# PowerBus.net
KiCad netlist of a schematic drawn in EAGLE
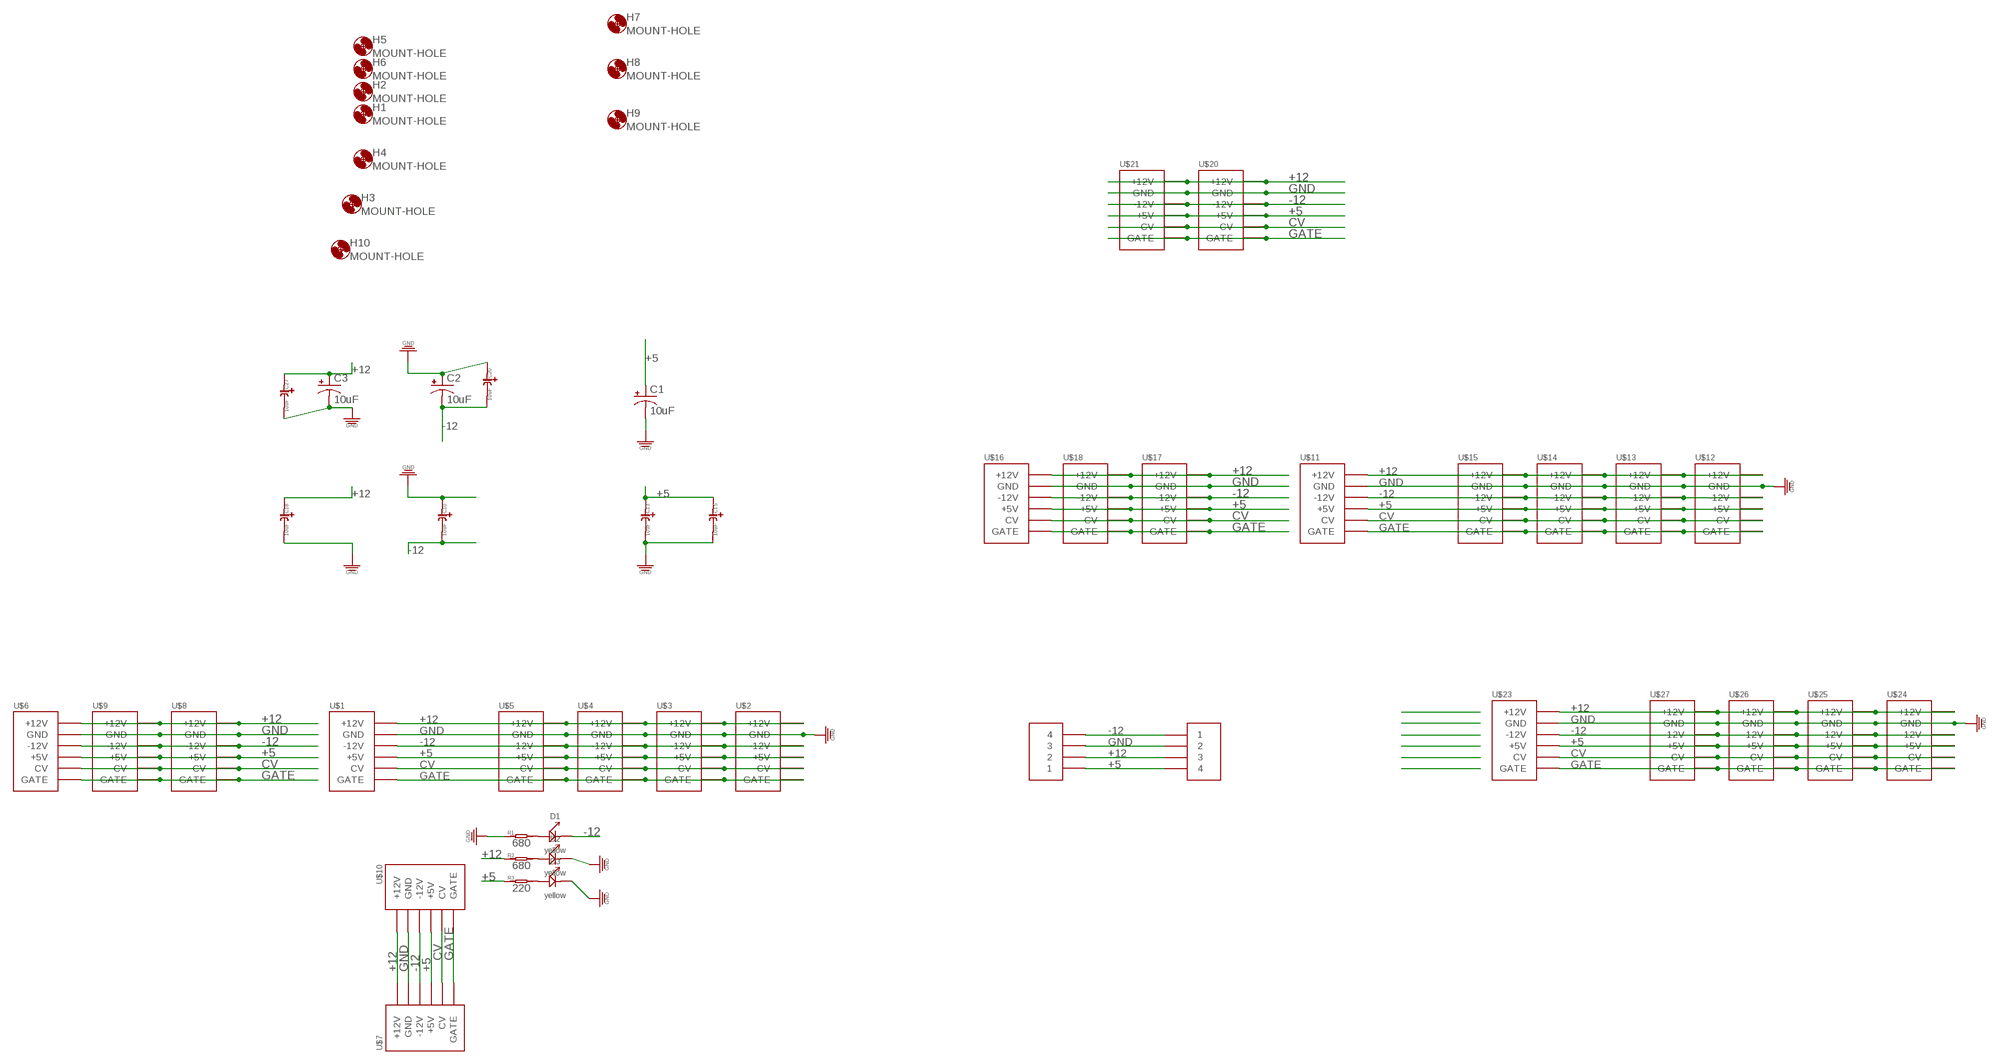
[diagram p0: schematic, sheet 1]

(export (version "E")
  (design (tool "Eeschema 10.0.6"))
  (components
    (comp (ref "C1")
      (value "10uF")
      (footprint "eagle-import:PANASONIC_D")
      (libsource (lib "eagle-import") (part "CAP_POLD"))
    )
    (comp (ref "C2")
      (value "10uF")
      (footprint "eagle-import:PANASONIC_D")
      (libsource (lib "eagle-import") (part "CAP_POLD"))
    )
    (comp (ref "C3")
      (value "10uF")
      (footprint "eagle-import:PANASONIC_D")
      (libsource (lib "eagle-import") (part "CAP_POLD"))
    )
    (comp (ref "C10")
      (value "10uF")
      (footprint "eagle-import:CASE-A_3216")
      (libsource (lib "eagle-import") (part "C-POLAR-A"))
    )
    (comp (ref "C13")
      (value "10uF")
      (footprint "eagle-import:CASE-A_3216")
      (libsource (lib "eagle-import") (part "C-POLAR-A"))
    )
    (comp (ref "C15")
      (value "10uF")
      (footprint "eagle-import:CASE-A_3216")
      (libsource (lib "eagle-import") (part "C-POLAR-A"))
    )
    (comp (ref "C18")
      (value "10uF")
      (footprint "eagle-import:CASE-A_3216")
      (libsource (lib "eagle-import") (part "C-POLAR-A"))
    )
    (comp (ref "C20")
      (value "10uF")
      (footprint "eagle-import:CASE-A_3216")
      (libsource (lib "eagle-import") (part "C-POLAR-A"))
    )
    (comp (ref "C27")
      (value "10uF")
      (footprint "eagle-import:CASE-A_3216")
      (libsource (lib "eagle-import") (part "C-POLAR-A"))
    )
    (comp (ref "D1")
      (value "yellow")
      (footprint "eagle-import:LED0603")
      (libsource (lib "eagle-import") (part "LED"))
    )
    (comp (ref "D2")
      (value "yellow")
      (footprint "eagle-import:LED0603")
      (libsource (lib "eagle-import") (part "LED"))
    )
    (comp (ref "D3")
      (value "yellow")
      (footprint "eagle-import:LED0603")
      (libsource (lib "eagle-import") (part "LED"))
    )
    (comp (ref "H1")
      (value "MOUNT-HOLE")
      (footprint "eagle-import:3.2-NOMARKINGS-SMALLSAFEZONE")
      (libsource (lib "eagle-import") (part "MOUNT-HOLE"))
    )
    (comp (ref "H2")
      (value "MOUNT-HOLE")
      (footprint "eagle-import:3.2-NOMARKINGS-SMALLSAFEZONE")
      (libsource (lib "eagle-import") (part "MOUNT-HOLE"))
    )
    (comp (ref "H3")
      (value "MOUNT-HOLE")
      (footprint "eagle-import:3.2-NOMARKINGS-SMALLSAFEZONE")
      (libsource (lib "eagle-import") (part "MOUNT-HOLE"))
    )
    (comp (ref "H4")
      (value "MOUNT-HOLE")
      (footprint "eagle-import:3.2-NOMARKINGS-SMALLSAFEZONE")
      (libsource (lib "eagle-import") (part "MOUNT-HOLE"))
    )
    (comp (ref "H5")
      (value "MOUNT-HOLE")
      (footprint "eagle-import:3.2-NOMARKINGS-SMALLSAFEZONE")
      (libsource (lib "eagle-import") (part "MOUNT-HOLE"))
    )
    (comp (ref "H6")
      (value "MOUNT-HOLE")
      (footprint "eagle-import:3.2-NOMARKINGS-SMALLSAFEZONE")
      (libsource (lib "eagle-import") (part "MOUNT-HOLE"))
    )
    (comp (ref "H7")
      (value "MOUNT-HOLE")
      (footprint "eagle-import:3.2-NOMARKINGS-SMALLSAFEZONE")
      (libsource (lib "eagle-import") (part "MOUNT-HOLE"))
    )
    (comp (ref "H8")
      (value "MOUNT-HOLE")
      (footprint "eagle-import:3.2-NOMARKINGS-SMALLSAFEZONE")
      (libsource (lib "eagle-import") (part "MOUNT-HOLE"))
    )
    (comp (ref "H9")
      (value "MOUNT-HOLE")
      (footprint "eagle-import:3.2-NOMARKINGS-SMALLSAFEZONE")
      (libsource (lib "eagle-import") (part "MOUNT-HOLE"))
    )
    (comp (ref "H10")
      (value "MOUNT-HOLE")
      (footprint "eagle-import:3.2-NOMARKINGS-SMALLSAFEZONE")
      (libsource (lib "eagle-import") (part "MOUNT-HOLE"))
    )
    (comp (ref "R1")
      (value "680")
      (footprint "eagle-import:R0603")
      (libsource (lib "eagle-import") (part "R-0603"))
    )
    (comp (ref "R2")
      (value "680")
      (footprint "eagle-import:R0603")
      (libsource (lib "eagle-import") (part "R-0603"))
    )
    (comp (ref "R3")
      (value "220")
      (footprint "eagle-import:R0603")
      (libsource (lib "eagle-import") (part "R-0603"))
    )
    (comp (ref "U$1")
      (value "POWER_SHROUDED_NOTEXT")
      (footprint "eagle-import:POWER_16_SHROUDED_NOTEXT")
      (libsource (lib "eagle-import") (part "POWER_SHROUDED_NOTEXT"))
    )
    (comp (ref "U$2")
      (value "POWER_SHROUDED_NOTEXT")
      (footprint "eagle-import:POWER_16_SHROUDED_NOTEXT")
      (libsource (lib "eagle-import") (part "POWER_SHROUDED_NOTEXT"))
    )
    (comp (ref "U$3")
      (value "POWER_SHROUDED_NOTEXT")
      (footprint "eagle-import:POWER_16_SHROUDED_NOTEXT")
      (libsource (lib "eagle-import") (part "POWER_SHROUDED_NOTEXT"))
    )
    (comp (ref "U$4")
      (value "POWER_SHROUDED_NOTEXT")
      (footprint "eagle-import:POWER_16_SHROUDED_NOTEXT")
      (libsource (lib "eagle-import") (part "POWER_SHROUDED_NOTEXT"))
    )
    (comp (ref "U$5")
      (value "POWER_SHROUDED_NOTEXT")
      (footprint "eagle-import:POWER_16_SHROUDED_NOTEXT")
      (libsource (lib "eagle-import") (part "POWER_SHROUDED_NOTEXT"))
    )
    (comp (ref "U$6")
      (value "POWER_SHROUDED_NOTEXT")
      (footprint "eagle-import:POWER_16_SHROUDED_NOTEXT")
      (libsource (lib "eagle-import") (part "POWER_SHROUDED_NOTEXT"))
    )
    (comp (ref "U$7")
      (value "POWER_SHROUDED_NOTEXT")
      (footprint "eagle-import:POWER_16_SHROUDED_NOTEXT")
      (libsource (lib "eagle-import") (part "POWER_SHROUDED_NOTEXT"))
    )
    (comp (ref "U$8")
      (value "POWER_SHROUDED_NOTEXT")
      (footprint "eagle-import:POWER_16_SHROUDED_NOTEXT")
      (libsource (lib "eagle-import") (part "POWER_SHROUDED_NOTEXT"))
    )
    (comp (ref "U$9")
      (value "POWER_SHROUDED_NOTEXT")
      (footprint "eagle-import:POWER_16_SHROUDED_NOTEXT")
      (libsource (lib "eagle-import") (part "POWER_SHROUDED_NOTEXT"))
    )
    (comp (ref "U$10")
      (value "POWER_SHROUDED_NOTEXT")
      (footprint "eagle-import:POWER_16_SHROUDED_NOTEXT")
      (libsource (lib "eagle-import") (part "POWER_SHROUDED_NOTEXT"))
    )
    (comp (ref "U$11")
      (value "POWER_SHROUDED_NOTEXT")
      (footprint "eagle-import:POWER_16_SHROUDED_NOTEXT")
      (libsource (lib "eagle-import") (part "POWER_SHROUDED_NOTEXT"))
    )
    (comp (ref "U$12")
      (value "POWER_SHROUDED_NOTEXT")
      (footprint "eagle-import:POWER_16_SHROUDED_NOTEXT")
      (libsource (lib "eagle-import") (part "POWER_SHROUDED_NOTEXT"))
    )
    (comp (ref "U$13")
      (value "POWER_SHROUDED_NOTEXT")
      (footprint "eagle-import:POWER_16_SHROUDED_NOTEXT")
      (libsource (lib "eagle-import") (part "POWER_SHROUDED_NOTEXT"))
    )
    (comp (ref "U$14")
      (value "POWER_SHROUDED_NOTEXT")
      (footprint "eagle-import:POWER_16_SHROUDED_NOTEXT")
      (libsource (lib "eagle-import") (part "POWER_SHROUDED_NOTEXT"))
    )
    (comp (ref "U$15")
      (value "POWER_SHROUDED_NOTEXT")
      (footprint "eagle-import:POWER_16_SHROUDED_NOTEXT")
      (libsource (lib "eagle-import") (part "POWER_SHROUDED_NOTEXT"))
    )
    (comp (ref "U$16")
      (value "POWER_SHROUDED_NOTEXT")
      (footprint "eagle-import:POWER_16_SHROUDED_NOTEXT")
      (libsource (lib "eagle-import") (part "POWER_SHROUDED_NOTEXT"))
    )
    (comp (ref "U$17")
      (value "POWER_SHROUDED_NOTEXT")
      (footprint "eagle-import:POWER_16_SHROUDED_NOTEXT")
      (libsource (lib "eagle-import") (part "POWER_SHROUDED_NOTEXT"))
    )
    (comp (ref "U$18")
      (value "POWER_SHROUDED_NOTEXT")
      (footprint "eagle-import:POWER_16_SHROUDED_NOTEXT")
      (libsource (lib "eagle-import") (part "POWER_SHROUDED_NOTEXT"))
    )
    (comp (ref "U$19")
      (value "4PIN5MM")
      (footprint "eagle-import:4PIN5MM")
      (libsource (lib "eagle-import") (part "4PIN5MM"))
    )
    (comp (ref "U$20")
      (value "POWER_SHROUDED_NOTEXT")
      (footprint "eagle-import:POWER_16_SHROUDED_NOTEXT")
      (libsource (lib "eagle-import") (part "POWER_SHROUDED_NOTEXT"))
    )
    (comp (ref "U$21")
      (value "POWER_SHROUDED_NOTEXT")
      (footprint "eagle-import:POWER_16_SHROUDED_NOTEXT")
      (libsource (lib "eagle-import") (part "POWER_SHROUDED_NOTEXT"))
    )
    (comp (ref "U$22")
      (value "4PIN5MM")
      (footprint "eagle-import:4PIN5MM")
      (libsource (lib "eagle-import") (part "4PIN5MM"))
    )
    (comp (ref "U$23")
      (value "POWER_SHROUDED_NOTEXT")
      (footprint "eagle-import:POWER_16_SHROUDED_NOTEXT")
      (libsource (lib "eagle-import") (part "POWER_SHROUDED_NOTEXT"))
    )
    (comp (ref "U$24")
      (value "POWER_SHROUDED_NOTEXT")
      (footprint "eagle-import:POWER_16_SHROUDED_NOTEXT")
      (libsource (lib "eagle-import") (part "POWER_SHROUDED_NOTEXT"))
    )
    (comp (ref "U$25")
      (value "POWER_SHROUDED_NOTEXT")
      (footprint "eagle-import:POWER_16_SHROUDED_NOTEXT")
      (libsource (lib "eagle-import") (part "POWER_SHROUDED_NOTEXT"))
    )
    (comp (ref "U$26")
      (value "POWER_SHROUDED_NOTEXT")
      (footprint "eagle-import:POWER_16_SHROUDED_NOTEXT")
      (libsource (lib "eagle-import") (part "POWER_SHROUDED_NOTEXT"))
    )
    (comp (ref "U$27")
      (value "POWER_SHROUDED_NOTEXT")
      (footprint "eagle-import:POWER_16_SHROUDED_NOTEXT")
      (libsource (lib "eagle-import") (part "POWER_SHROUDED_NOTEXT"))
    )
  )
  (nets
    (net (code "1") (name "/+5") (class "Default")
      (node (ref "C1") (pin "+") (pinfunction "+_+") (pintype "passive"))
      (node (ref "C13") (pin "+") (pinfunction "1_+") (pintype "bidirectional"))
      (node (ref "C15") (pin "+") (pinfunction "1_+") (pintype "bidirectional"))
      (node (ref "R3") (pin "1") (pinfunction "1_1") (pintype "bidirectional"))
      (node (ref "U$1") (pin "11") (pinfunction "+5V_11") (pintype "bidirectional"))
      (node (ref "U$1") (pin "12") (pinfunction "+5V_12") (pintype "bidirectional"))
      (node (ref "U$10") (pin "11") (pinfunction "+5V_11") (pintype "bidirectional"))
      (node (ref "U$10") (pin "12") (pinfunction "+5V_12") (pintype "bidirectional"))
      (node (ref "U$11") (pin "11") (pinfunction "+5V_11") (pintype "bidirectional"))
      (node (ref "U$11") (pin "12") (pinfunction "+5V_12") (pintype "bidirectional"))
      (node (ref "U$12") (pin "11") (pinfunction "+5V_11") (pintype "bidirectional"))
      (node (ref "U$12") (pin "12") (pinfunction "+5V_12") (pintype "bidirectional"))
      (node (ref "U$13") (pin "11") (pinfunction "+5V_11") (pintype "bidirectional"))
      (node (ref "U$13") (pin "12") (pinfunction "+5V_12") (pintype "bidirectional"))
      (node (ref "U$14") (pin "11") (pinfunction "+5V_11") (pintype "bidirectional"))
      (node (ref "U$14") (pin "12") (pinfunction "+5V_12") (pintype "bidirectional"))
      (node (ref "U$15") (pin "11") (pinfunction "+5V_11") (pintype "bidirectional"))
      (node (ref "U$15") (pin "12") (pinfunction "+5V_12") (pintype "bidirectional"))
      (node (ref "U$16") (pin "11") (pinfunction "+5V_11") (pintype "bidirectional"))
      (node (ref "U$16") (pin "12") (pinfunction "+5V_12") (pintype "bidirectional"))
      (node (ref "U$17") (pin "11") (pinfunction "+5V_11") (pintype "bidirectional"))
      (node (ref "U$17") (pin "12") (pinfunction "+5V_12") (pintype "bidirectional"))
      (node (ref "U$18") (pin "11") (pinfunction "+5V_11") (pintype "bidirectional"))
      (node (ref "U$18") (pin "12") (pinfunction "+5V_12") (pintype "bidirectional"))
      (node (ref "U$19") (pin "4") (pinfunction "4_4") (pintype "bidirectional"))
      (node (ref "U$2") (pin "11") (pinfunction "+5V_11") (pintype "bidirectional"))
      (node (ref "U$2") (pin "12") (pinfunction "+5V_12") (pintype "bidirectional"))
      (node (ref "U$20") (pin "11") (pinfunction "+5V_11") (pintype "bidirectional"))
      (node (ref "U$20") (pin "12") (pinfunction "+5V_12") (pintype "bidirectional"))
      (node (ref "U$21") (pin "11") (pinfunction "+5V_11") (pintype "bidirectional"))
      (node (ref "U$21") (pin "12") (pinfunction "+5V_12") (pintype "bidirectional"))
      (node (ref "U$22") (pin "1") (pinfunction "1_1") (pintype "bidirectional"))
      (node (ref "U$23") (pin "11") (pinfunction "+5V_11") (pintype "bidirectional"))
      (node (ref "U$23") (pin "12") (pinfunction "+5V_12") (pintype "bidirectional"))
      (node (ref "U$24") (pin "11") (pinfunction "+5V_11") (pintype "bidirectional"))
      (node (ref "U$24") (pin "12") (pinfunction "+5V_12") (pintype "bidirectional"))
      (node (ref "U$25") (pin "11") (pinfunction "+5V_11") (pintype "bidirectional"))
      (node (ref "U$25") (pin "12") (pinfunction "+5V_12") (pintype "bidirectional"))
      (node (ref "U$26") (pin "11") (pinfunction "+5V_11") (pintype "bidirectional"))
      (node (ref "U$26") (pin "12") (pinfunction "+5V_12") (pintype "bidirectional"))
      (node (ref "U$27") (pin "11") (pinfunction "+5V_11") (pintype "bidirectional"))
      (node (ref "U$27") (pin "12") (pinfunction "+5V_12") (pintype "bidirectional"))
      (node (ref "U$3") (pin "11") (pinfunction "+5V_11") (pintype "bidirectional"))
      (node (ref "U$3") (pin "12") (pinfunction "+5V_12") (pintype "bidirectional"))
      (node (ref "U$4") (pin "11") (pinfunction "+5V_11") (pintype "bidirectional"))
      (node (ref "U$4") (pin "12") (pinfunction "+5V_12") (pintype "bidirectional"))
      (node (ref "U$5") (pin "11") (pinfunction "+5V_11") (pintype "bidirectional"))
      (node (ref "U$5") (pin "12") (pinfunction "+5V_12") (pintype "bidirectional"))
      (node (ref "U$6") (pin "11") (pinfunction "+5V_11") (pintype "bidirectional"))
      (node (ref "U$6") (pin "12") (pinfunction "+5V_12") (pintype "bidirectional"))
      (node (ref "U$7") (pin "11") (pinfunction "+5V_11") (pintype "bidirectional"))
      (node (ref "U$7") (pin "12") (pinfunction "+5V_12") (pintype "bidirectional"))
      (node (ref "U$8") (pin "11") (pinfunction "+5V_11") (pintype "bidirectional"))
      (node (ref "U$8") (pin "12") (pinfunction "+5V_12") (pintype "bidirectional"))
      (node (ref "U$9") (pin "11") (pinfunction "+5V_11") (pintype "bidirectional"))
      (node (ref "U$9") (pin "12") (pinfunction "+5V_12") (pintype "bidirectional"))
    )
    (net (code "2") (name "/+12") (class "Default")
      (node (ref "C18") (pin "+") (pinfunction "1_+") (pintype "bidirectional"))
      (node (ref "C27") (pin "+") (pinfunction "1_+") (pintype "bidirectional"))
      (node (ref "C3") (pin "+") (pinfunction "+_+") (pintype "passive"))
      (node (ref "R2") (pin "1") (pinfunction "1_1") (pintype "bidirectional"))
      (node (ref "U$1") (pin "10") (pinfunction "+12V_10") (pintype "bidirectional"))
      (node (ref "U$1") (pin "9") (pinfunction "+12V_9") (pintype "bidirectional"))
      (node (ref "U$10") (pin "10") (pinfunction "+12V_10") (pintype "bidirectional"))
      (node (ref "U$10") (pin "9") (pinfunction "+12V_9") (pintype "bidirectional"))
      (node (ref "U$11") (pin "10") (pinfunction "+12V_10") (pintype "bidirectional"))
      (node (ref "U$11") (pin "9") (pinfunction "+12V_9") (pintype "bidirectional"))
      (node (ref "U$12") (pin "10") (pinfunction "+12V_10") (pintype "bidirectional"))
      (node (ref "U$12") (pin "9") (pinfunction "+12V_9") (pintype "bidirectional"))
      (node (ref "U$13") (pin "10") (pinfunction "+12V_10") (pintype "bidirectional"))
      (node (ref "U$13") (pin "9") (pinfunction "+12V_9") (pintype "bidirectional"))
      (node (ref "U$14") (pin "10") (pinfunction "+12V_10") (pintype "bidirectional"))
      (node (ref "U$14") (pin "9") (pinfunction "+12V_9") (pintype "bidirectional"))
      (node (ref "U$15") (pin "10") (pinfunction "+12V_10") (pintype "bidirectional"))
      (node (ref "U$15") (pin "9") (pinfunction "+12V_9") (pintype "bidirectional"))
      (node (ref "U$16") (pin "10") (pinfunction "+12V_10") (pintype "bidirectional"))
      (node (ref "U$16") (pin "9") (pinfunction "+12V_9") (pintype "bidirectional"))
      (node (ref "U$17") (pin "10") (pinfunction "+12V_10") (pintype "bidirectional"))
      (node (ref "U$17") (pin "9") (pinfunction "+12V_9") (pintype "bidirectional"))
      (node (ref "U$18") (pin "10") (pinfunction "+12V_10") (pintype "bidirectional"))
      (node (ref "U$18") (pin "9") (pinfunction "+12V_9") (pintype "bidirectional"))
      (node (ref "U$19") (pin "3") (pinfunction "3_3") (pintype "bidirectional"))
      (node (ref "U$2") (pin "10") (pinfunction "+12V_10") (pintype "bidirectional"))
      (node (ref "U$2") (pin "9") (pinfunction "+12V_9") (pintype "bidirectional"))
      (node (ref "U$20") (pin "10") (pinfunction "+12V_10") (pintype "bidirectional"))
      (node (ref "U$20") (pin "9") (pinfunction "+12V_9") (pintype "bidirectional"))
      (node (ref "U$21") (pin "10") (pinfunction "+12V_10") (pintype "bidirectional"))
      (node (ref "U$21") (pin "9") (pinfunction "+12V_9") (pintype "bidirectional"))
      (node (ref "U$22") (pin "2") (pinfunction "2_2") (pintype "bidirectional"))
      (node (ref "U$23") (pin "10") (pinfunction "+12V_10") (pintype "bidirectional"))
      (node (ref "U$23") (pin "9") (pinfunction "+12V_9") (pintype "bidirectional"))
      (node (ref "U$24") (pin "10") (pinfunction "+12V_10") (pintype "bidirectional"))
      (node (ref "U$24") (pin "9") (pinfunction "+12V_9") (pintype "bidirectional"))
      (node (ref "U$25") (pin "10") (pinfunction "+12V_10") (pintype "bidirectional"))
      (node (ref "U$25") (pin "9") (pinfunction "+12V_9") (pintype "bidirectional"))
      (node (ref "U$26") (pin "10") (pinfunction "+12V_10") (pintype "bidirectional"))
      (node (ref "U$26") (pin "9") (pinfunction "+12V_9") (pintype "bidirectional"))
      (node (ref "U$27") (pin "10") (pinfunction "+12V_10") (pintype "bidirectional"))
      (node (ref "U$27") (pin "9") (pinfunction "+12V_9") (pintype "bidirectional"))
      (node (ref "U$3") (pin "10") (pinfunction "+12V_10") (pintype "bidirectional"))
      (node (ref "U$3") (pin "9") (pinfunction "+12V_9") (pintype "bidirectional"))
      (node (ref "U$4") (pin "10") (pinfunction "+12V_10") (pintype "bidirectional"))
      (node (ref "U$4") (pin "9") (pinfunction "+12V_9") (pintype "bidirectional"))
      (node (ref "U$5") (pin "10") (pinfunction "+12V_10") (pintype "bidirectional"))
      (node (ref "U$5") (pin "9") (pinfunction "+12V_9") (pintype "bidirectional"))
      (node (ref "U$6") (pin "10") (pinfunction "+12V_10") (pintype "bidirectional"))
      (node (ref "U$6") (pin "9") (pinfunction "+12V_9") (pintype "bidirectional"))
      (node (ref "U$7") (pin "10") (pinfunction "+12V_10") (pintype "bidirectional"))
      (node (ref "U$7") (pin "9") (pinfunction "+12V_9") (pintype "bidirectional"))
      (node (ref "U$8") (pin "10") (pinfunction "+12V_10") (pintype "bidirectional"))
      (node (ref "U$8") (pin "9") (pinfunction "+12V_9") (pintype "bidirectional"))
      (node (ref "U$9") (pin "10") (pinfunction "+12V_10") (pintype "bidirectional"))
      (node (ref "U$9") (pin "9") (pinfunction "+12V_9") (pintype "bidirectional"))
    )
    (net (code "3") (name "/-12") (class "Default")
      (node (ref "C10") (pin "-") (pinfunction "2_-") (pintype "bidirectional"))
      (node (ref "C2") (pin "-") (pinfunction "-_-") (pintype "passive"))
      (node (ref "C20") (pin "-") (pinfunction "2_-") (pintype "bidirectional"))
      (node (ref "D1") (pin "-") (pinfunction "-_-") (pintype "passive"))
      (node (ref "U$1") (pin "1") (pinfunction "-12V_1") (pintype "bidirectional"))
      (node (ref "U$1") (pin "2") (pinfunction "-12V_2") (pintype "bidirectional"))
      (node (ref "U$10") (pin "1") (pinfunction "-12V_1") (pintype "bidirectional"))
      (node (ref "U$10") (pin "2") (pinfunction "-12V_2") (pintype "bidirectional"))
      (node (ref "U$11") (pin "1") (pinfunction "-12V_1") (pintype "bidirectional"))
      (node (ref "U$11") (pin "2") (pinfunction "-12V_2") (pintype "bidirectional"))
      (node (ref "U$12") (pin "1") (pinfunction "-12V_1") (pintype "bidirectional"))
      (node (ref "U$12") (pin "2") (pinfunction "-12V_2") (pintype "bidirectional"))
      (node (ref "U$13") (pin "1") (pinfunction "-12V_1") (pintype "bidirectional"))
      (node (ref "U$13") (pin "2") (pinfunction "-12V_2") (pintype "bidirectional"))
      (node (ref "U$14") (pin "1") (pinfunction "-12V_1") (pintype "bidirectional"))
      (node (ref "U$14") (pin "2") (pinfunction "-12V_2") (pintype "bidirectional"))
      (node (ref "U$15") (pin "1") (pinfunction "-12V_1") (pintype "bidirectional"))
      (node (ref "U$15") (pin "2") (pinfunction "-12V_2") (pintype "bidirectional"))
      (node (ref "U$16") (pin "1") (pinfunction "-12V_1") (pintype "bidirectional"))
      (node (ref "U$16") (pin "2") (pinfunction "-12V_2") (pintype "bidirectional"))
      (node (ref "U$17") (pin "1") (pinfunction "-12V_1") (pintype "bidirectional"))
      (node (ref "U$17") (pin "2") (pinfunction "-12V_2") (pintype "bidirectional"))
      (node (ref "U$18") (pin "1") (pinfunction "-12V_1") (pintype "bidirectional"))
      (node (ref "U$18") (pin "2") (pinfunction "-12V_2") (pintype "bidirectional"))
      (node (ref "U$19") (pin "1") (pinfunction "1_1") (pintype "bidirectional"))
      (node (ref "U$2") (pin "1") (pinfunction "-12V_1") (pintype "bidirectional"))
      (node (ref "U$2") (pin "2") (pinfunction "-12V_2") (pintype "bidirectional"))
      (node (ref "U$20") (pin "1") (pinfunction "-12V_1") (pintype "bidirectional"))
      (node (ref "U$20") (pin "2") (pinfunction "-12V_2") (pintype "bidirectional"))
      (node (ref "U$21") (pin "1") (pinfunction "-12V_1") (pintype "bidirectional"))
      (node (ref "U$21") (pin "2") (pinfunction "-12V_2") (pintype "bidirectional"))
      (node (ref "U$22") (pin "4") (pinfunction "4_4") (pintype "bidirectional"))
      (node (ref "U$23") (pin "1") (pinfunction "-12V_1") (pintype "bidirectional"))
      (node (ref "U$23") (pin "2") (pinfunction "-12V_2") (pintype "bidirectional"))
      (node (ref "U$24") (pin "1") (pinfunction "-12V_1") (pintype "bidirectional"))
      (node (ref "U$24") (pin "2") (pinfunction "-12V_2") (pintype "bidirectional"))
      (node (ref "U$25") (pin "1") (pinfunction "-12V_1") (pintype "bidirectional"))
      (node (ref "U$25") (pin "2") (pinfunction "-12V_2") (pintype "bidirectional"))
      (node (ref "U$26") (pin "1") (pinfunction "-12V_1") (pintype "bidirectional"))
      (node (ref "U$26") (pin "2") (pinfunction "-12V_2") (pintype "bidirectional"))
      (node (ref "U$27") (pin "1") (pinfunction "-12V_1") (pintype "bidirectional"))
      (node (ref "U$27") (pin "2") (pinfunction "-12V_2") (pintype "bidirectional"))
      (node (ref "U$3") (pin "1") (pinfunction "-12V_1") (pintype "bidirectional"))
      (node (ref "U$3") (pin "2") (pinfunction "-12V_2") (pintype "bidirectional"))
      (node (ref "U$4") (pin "1") (pinfunction "-12V_1") (pintype "bidirectional"))
      (node (ref "U$4") (pin "2") (pinfunction "-12V_2") (pintype "bidirectional"))
      (node (ref "U$5") (pin "1") (pinfunction "-12V_1") (pintype "bidirectional"))
      (node (ref "U$5") (pin "2") (pinfunction "-12V_2") (pintype "bidirectional"))
      (node (ref "U$6") (pin "1") (pinfunction "-12V_1") (pintype "bidirectional"))
      (node (ref "U$6") (pin "2") (pinfunction "-12V_2") (pintype "bidirectional"))
      (node (ref "U$7") (pin "1") (pinfunction "-12V_1") (pintype "bidirectional"))
      (node (ref "U$7") (pin "2") (pinfunction "-12V_2") (pintype "bidirectional"))
      (node (ref "U$8") (pin "1") (pinfunction "-12V_1") (pintype "bidirectional"))
      (node (ref "U$8") (pin "2") (pinfunction "-12V_2") (pintype "bidirectional"))
      (node (ref "U$9") (pin "1") (pinfunction "-12V_1") (pintype "bidirectional"))
      (node (ref "U$9") (pin "2") (pinfunction "-12V_2") (pintype "bidirectional"))
    )
    (net (code "4") (name "/CV") (class "Default")
      (node (ref "U$1") (pin "13") (pinfunction "CV_13") (pintype "bidirectional"))
      (node (ref "U$1") (pin "14") (pinfunction "CV_14") (pintype "bidirectional"))
      (node (ref "U$10") (pin "13") (pinfunction "CV_13") (pintype "bidirectional"))
      (node (ref "U$10") (pin "14") (pinfunction "CV_14") (pintype "bidirectional"))
      (node (ref "U$11") (pin "13") (pinfunction "CV_13") (pintype "bidirectional"))
      (node (ref "U$11") (pin "14") (pinfunction "CV_14") (pintype "bidirectional"))
      (node (ref "U$12") (pin "13") (pinfunction "CV_13") (pintype "bidirectional"))
      (node (ref "U$12") (pin "14") (pinfunction "CV_14") (pintype "bidirectional"))
      (node (ref "U$13") (pin "13") (pinfunction "CV_13") (pintype "bidirectional"))
      (node (ref "U$13") (pin "14") (pinfunction "CV_14") (pintype "bidirectional"))
      (node (ref "U$14") (pin "13") (pinfunction "CV_13") (pintype "bidirectional"))
      (node (ref "U$14") (pin "14") (pinfunction "CV_14") (pintype "bidirectional"))
      (node (ref "U$15") (pin "13") (pinfunction "CV_13") (pintype "bidirectional"))
      (node (ref "U$15") (pin "14") (pinfunction "CV_14") (pintype "bidirectional"))
      (node (ref "U$16") (pin "13") (pinfunction "CV_13") (pintype "bidirectional"))
      (node (ref "U$16") (pin "14") (pinfunction "CV_14") (pintype "bidirectional"))
      (node (ref "U$17") (pin "13") (pinfunction "CV_13") (pintype "bidirectional"))
      (node (ref "U$17") (pin "14") (pinfunction "CV_14") (pintype "bidirectional"))
      (node (ref "U$18") (pin "13") (pinfunction "CV_13") (pintype "bidirectional"))
      (node (ref "U$18") (pin "14") (pinfunction "CV_14") (pintype "bidirectional"))
      (node (ref "U$2") (pin "13") (pinfunction "CV_13") (pintype "bidirectional"))
      (node (ref "U$2") (pin "14") (pinfunction "CV_14") (pintype "bidirectional"))
      (node (ref "U$20") (pin "13") (pinfunction "CV_13") (pintype "bidirectional"))
      (node (ref "U$20") (pin "14") (pinfunction "CV_14") (pintype "bidirectional"))
      (node (ref "U$21") (pin "13") (pinfunction "CV_13") (pintype "bidirectional"))
      (node (ref "U$21") (pin "14") (pinfunction "CV_14") (pintype "bidirectional"))
      (node (ref "U$23") (pin "13") (pinfunction "CV_13") (pintype "bidirectional"))
      (node (ref "U$23") (pin "14") (pinfunction "CV_14") (pintype "bidirectional"))
      (node (ref "U$24") (pin "13") (pinfunction "CV_13") (pintype "bidirectional"))
      (node (ref "U$24") (pin "14") (pinfunction "CV_14") (pintype "bidirectional"))
      (node (ref "U$25") (pin "13") (pinfunction "CV_13") (pintype "bidirectional"))
      (node (ref "U$25") (pin "14") (pinfunction "CV_14") (pintype "bidirectional"))
      (node (ref "U$26") (pin "13") (pinfunction "CV_13") (pintype "bidirectional"))
      (node (ref "U$26") (pin "14") (pinfunction "CV_14") (pintype "bidirectional"))
      (node (ref "U$27") (pin "13") (pinfunction "CV_13") (pintype "bidirectional"))
      (node (ref "U$27") (pin "14") (pinfunction "CV_14") (pintype "bidirectional"))
      (node (ref "U$3") (pin "13") (pinfunction "CV_13") (pintype "bidirectional"))
      (node (ref "U$3") (pin "14") (pinfunction "CV_14") (pintype "bidirectional"))
      (node (ref "U$4") (pin "13") (pinfunction "CV_13") (pintype "bidirectional"))
      (node (ref "U$4") (pin "14") (pinfunction "CV_14") (pintype "bidirectional"))
      (node (ref "U$5") (pin "13") (pinfunction "CV_13") (pintype "bidirectional"))
      (node (ref "U$5") (pin "14") (pinfunction "CV_14") (pintype "bidirectional"))
      (node (ref "U$6") (pin "13") (pinfunction "CV_13") (pintype "bidirectional"))
      (node (ref "U$6") (pin "14") (pinfunction "CV_14") (pintype "bidirectional"))
      (node (ref "U$7") (pin "13") (pinfunction "CV_13") (pintype "bidirectional"))
      (node (ref "U$7") (pin "14") (pinfunction "CV_14") (pintype "bidirectional"))
      (node (ref "U$8") (pin "13") (pinfunction "CV_13") (pintype "bidirectional"))
      (node (ref "U$8") (pin "14") (pinfunction "CV_14") (pintype "bidirectional"))
      (node (ref "U$9") (pin "13") (pinfunction "CV_13") (pintype "bidirectional"))
      (node (ref "U$9") (pin "14") (pinfunction "CV_14") (pintype "bidirectional"))
    )
    (net (code "5") (name "/GATE") (class "Default")
      (node (ref "U$1") (pin "15") (pinfunction "GATE_15") (pintype "bidirectional"))
      (node (ref "U$1") (pin "16") (pinfunction "GATE_16") (pintype "bidirectional"))
      (node (ref "U$10") (pin "15") (pinfunction "GATE_15") (pintype "bidirectional"))
      (node (ref "U$10") (pin "16") (pinfunction "GATE_16") (pintype "bidirectional"))
      (node (ref "U$11") (pin "15") (pinfunction "GATE_15") (pintype "bidirectional"))
      (node (ref "U$11") (pin "16") (pinfunction "GATE_16") (pintype "bidirectional"))
      (node (ref "U$12") (pin "15") (pinfunction "GATE_15") (pintype "bidirectional"))
      (node (ref "U$12") (pin "16") (pinfunction "GATE_16") (pintype "bidirectional"))
      (node (ref "U$13") (pin "15") (pinfunction "GATE_15") (pintype "bidirectional"))
      (node (ref "U$13") (pin "16") (pinfunction "GATE_16") (pintype "bidirectional"))
      (node (ref "U$14") (pin "15") (pinfunction "GATE_15") (pintype "bidirectional"))
      (node (ref "U$14") (pin "16") (pinfunction "GATE_16") (pintype "bidirectional"))
      (node (ref "U$15") (pin "15") (pinfunction "GATE_15") (pintype "bidirectional"))
      (node (ref "U$15") (pin "16") (pinfunction "GATE_16") (pintype "bidirectional"))
      (node (ref "U$16") (pin "15") (pinfunction "GATE_15") (pintype "bidirectional"))
      (node (ref "U$16") (pin "16") (pinfunction "GATE_16") (pintype "bidirectional"))
      (node (ref "U$17") (pin "15") (pinfunction "GATE_15") (pintype "bidirectional"))
      (node (ref "U$17") (pin "16") (pinfunction "GATE_16") (pintype "bidirectional"))
      (node (ref "U$18") (pin "15") (pinfunction "GATE_15") (pintype "bidirectional"))
      (node (ref "U$18") (pin "16") (pinfunction "GATE_16") (pintype "bidirectional"))
      (node (ref "U$2") (pin "15") (pinfunction "GATE_15") (pintype "bidirectional"))
      (node (ref "U$2") (pin "16") (pinfunction "GATE_16") (pintype "bidirectional"))
      (node (ref "U$20") (pin "15") (pinfunction "GATE_15") (pintype "bidirectional"))
      (node (ref "U$20") (pin "16") (pinfunction "GATE_16") (pintype "bidirectional"))
      (node (ref "U$21") (pin "15") (pinfunction "GATE_15") (pintype "bidirectional"))
      (node (ref "U$21") (pin "16") (pinfunction "GATE_16") (pintype "bidirectional"))
      (node (ref "U$23") (pin "15") (pinfunction "GATE_15") (pintype "bidirectional"))
      (node (ref "U$23") (pin "16") (pinfunction "GATE_16") (pintype "bidirectional"))
      (node (ref "U$24") (pin "15") (pinfunction "GATE_15") (pintype "bidirectional"))
      (node (ref "U$24") (pin "16") (pinfunction "GATE_16") (pintype "bidirectional"))
      (node (ref "U$25") (pin "15") (pinfunction "GATE_15") (pintype "bidirectional"))
      (node (ref "U$25") (pin "16") (pinfunction "GATE_16") (pintype "bidirectional"))
      (node (ref "U$26") (pin "15") (pinfunction "GATE_15") (pintype "bidirectional"))
      (node (ref "U$26") (pin "16") (pinfunction "GATE_16") (pintype "bidirectional"))
      (node (ref "U$27") (pin "15") (pinfunction "GATE_15") (pintype "bidirectional"))
      (node (ref "U$27") (pin "16") (pinfunction "GATE_16") (pintype "bidirectional"))
      (node (ref "U$3") (pin "15") (pinfunction "GATE_15") (pintype "bidirectional"))
      (node (ref "U$3") (pin "16") (pinfunction "GATE_16") (pintype "bidirectional"))
      (node (ref "U$4") (pin "15") (pinfunction "GATE_15") (pintype "bidirectional"))
      (node (ref "U$4") (pin "16") (pinfunction "GATE_16") (pintype "bidirectional"))
      (node (ref "U$5") (pin "15") (pinfunction "GATE_15") (pintype "bidirectional"))
      (node (ref "U$5") (pin "16") (pinfunction "GATE_16") (pintype "bidirectional"))
      (node (ref "U$6") (pin "15") (pinfunction "GATE_15") (pintype "bidirectional"))
      (node (ref "U$6") (pin "16") (pinfunction "GATE_16") (pintype "bidirectional"))
      (node (ref "U$7") (pin "15") (pinfunction "GATE_15") (pintype "bidirectional"))
      (node (ref "U$7") (pin "16") (pinfunction "GATE_16") (pintype "bidirectional"))
      (node (ref "U$8") (pin "15") (pinfunction "GATE_15") (pintype "bidirectional"))
      (node (ref "U$8") (pin "16") (pinfunction "GATE_16") (pintype "bidirectional"))
      (node (ref "U$9") (pin "15") (pinfunction "GATE_15") (pintype "bidirectional"))
      (node (ref "U$9") (pin "16") (pinfunction "GATE_16") (pintype "bidirectional"))
    )
    (net (code "6") (name "GND") (class "Default")
      (node (ref "C1") (pin "-") (pinfunction "-_-") (pintype "passive"))
      (node (ref "C10") (pin "+") (pinfunction "1_+") (pintype "bidirectional"))
      (node (ref "C13") (pin "-") (pinfunction "2_-") (pintype "bidirectional"))
      (node (ref "C15") (pin "-") (pinfunction "2_-") (pintype "bidirectional"))
      (node (ref "C18") (pin "-") (pinfunction "2_-") (pintype "bidirectional"))
      (node (ref "C2") (pin "+") (pinfunction "+_+") (pintype "passive"))
      (node (ref "C20") (pin "+") (pinfunction "1_+") (pintype "bidirectional"))
      (node (ref "C27") (pin "-") (pinfunction "2_-") (pintype "bidirectional"))
      (node (ref "C3") (pin "-") (pinfunction "-_-") (pintype "passive"))
      (node (ref "D2") (pin "-") (pinfunction "-_-") (pintype "passive"))
      (node (ref "D3") (pin "-") (pinfunction "-_-") (pintype "passive"))
      (node (ref "R1") (pin "1") (pinfunction "1_1") (pintype "bidirectional"))
      (node (ref "U$1") (pin "3") (pinfunction "GND_3") (pintype "bidirectional"))
      (node (ref "U$1") (pin "4") (pinfunction "GND_4") (pintype "bidirectional"))
      (node (ref "U$1") (pin "5") (pinfunction "GND_5") (pintype "bidirectional"))
      (node (ref "U$1") (pin "6") (pinfunction "GND_6") (pintype "bidirectional"))
      (node (ref "U$1") (pin "7") (pinfunction "GND_7") (pintype "bidirectional"))
      (node (ref "U$1") (pin "8") (pinfunction "GND_8") (pintype "bidirectional"))
      (node (ref "U$10") (pin "3") (pinfunction "GND_3") (pintype "bidirectional"))
      (node (ref "U$10") (pin "4") (pinfunction "GND_4") (pintype "bidirectional"))
      (node (ref "U$10") (pin "5") (pinfunction "GND_5") (pintype "bidirectional"))
      (node (ref "U$10") (pin "6") (pinfunction "GND_6") (pintype "bidirectional"))
      (node (ref "U$10") (pin "7") (pinfunction "GND_7") (pintype "bidirectional"))
      (node (ref "U$10") (pin "8") (pinfunction "GND_8") (pintype "bidirectional"))
      (node (ref "U$11") (pin "3") (pinfunction "GND_3") (pintype "bidirectional"))
      (node (ref "U$11") (pin "4") (pinfunction "GND_4") (pintype "bidirectional"))
      (node (ref "U$11") (pin "5") (pinfunction "GND_5") (pintype "bidirectional"))
      (node (ref "U$11") (pin "6") (pinfunction "GND_6") (pintype "bidirectional"))
      (node (ref "U$11") (pin "7") (pinfunction "GND_7") (pintype "bidirectional"))
      (node (ref "U$11") (pin "8") (pinfunction "GND_8") (pintype "bidirectional"))
      (node (ref "U$12") (pin "3") (pinfunction "GND_3") (pintype "bidirectional"))
      (node (ref "U$12") (pin "4") (pinfunction "GND_4") (pintype "bidirectional"))
      (node (ref "U$12") (pin "5") (pinfunction "GND_5") (pintype "bidirectional"))
      (node (ref "U$12") (pin "6") (pinfunction "GND_6") (pintype "bidirectional"))
      (node (ref "U$12") (pin "7") (pinfunction "GND_7") (pintype "bidirectional"))
      (node (ref "U$12") (pin "8") (pinfunction "GND_8") (pintype "bidirectional"))
      (node (ref "U$13") (pin "3") (pinfunction "GND_3") (pintype "bidirectional"))
      (node (ref "U$13") (pin "4") (pinfunction "GND_4") (pintype "bidirectional"))
      (node (ref "U$13") (pin "5") (pinfunction "GND_5") (pintype "bidirectional"))
      (node (ref "U$13") (pin "6") (pinfunction "GND_6") (pintype "bidirectional"))
      (node (ref "U$13") (pin "7") (pinfunction "GND_7") (pintype "bidirectional"))
      (node (ref "U$13") (pin "8") (pinfunction "GND_8") (pintype "bidirectional"))
      (node (ref "U$14") (pin "3") (pinfunction "GND_3") (pintype "bidirectional"))
      (node (ref "U$14") (pin "4") (pinfunction "GND_4") (pintype "bidirectional"))
      (node (ref "U$14") (pin "5") (pinfunction "GND_5") (pintype "bidirectional"))
      (node (ref "U$14") (pin "6") (pinfunction "GND_6") (pintype "bidirectional"))
      (node (ref "U$14") (pin "7") (pinfunction "GND_7") (pintype "bidirectional"))
      (node (ref "U$14") (pin "8") (pinfunction "GND_8") (pintype "bidirectional"))
      (node (ref "U$15") (pin "3") (pinfunction "GND_3") (pintype "bidirectional"))
      (node (ref "U$15") (pin "4") (pinfunction "GND_4") (pintype "bidirectional"))
      (node (ref "U$15") (pin "5") (pinfunction "GND_5") (pintype "bidirectional"))
      (node (ref "U$15") (pin "6") (pinfunction "GND_6") (pintype "bidirectional"))
      (node (ref "U$15") (pin "7") (pinfunction "GND_7") (pintype "bidirectional"))
      (node (ref "U$15") (pin "8") (pinfunction "GND_8") (pintype "bidirectional"))
      (node (ref "U$16") (pin "3") (pinfunction "GND_3") (pintype "bidirectional"))
      (node (ref "U$16") (pin "4") (pinfunction "GND_4") (pintype "bidirectional"))
      (node (ref "U$16") (pin "5") (pinfunction "GND_5") (pintype "bidirectional"))
      (node (ref "U$16") (pin "6") (pinfunction "GND_6") (pintype "bidirectional"))
      (node (ref "U$16") (pin "7") (pinfunction "GND_7") (pintype "bidirectional"))
      (node (ref "U$16") (pin "8") (pinfunction "GND_8") (pintype "bidirectional"))
      (node (ref "U$17") (pin "3") (pinfunction "GND_3") (pintype "bidirectional"))
      (node (ref "U$17") (pin "4") (pinfunction "GND_4") (pintype "bidirectional"))
      (node (ref "U$17") (pin "5") (pinfunction "GND_5") (pintype "bidirectional"))
      (node (ref "U$17") (pin "6") (pinfunction "GND_6") (pintype "bidirectional"))
      (node (ref "U$17") (pin "7") (pinfunction "GND_7") (pintype "bidirectional"))
      (node (ref "U$17") (pin "8") (pinfunction "GND_8") (pintype "bidirectional"))
      (node (ref "U$18") (pin "3") (pinfunction "GND_3") (pintype "bidirectional"))
      (node (ref "U$18") (pin "4") (pinfunction "GND_4") (pintype "bidirectional"))
      (node (ref "U$18") (pin "5") (pinfunction "GND_5") (pintype "bidirectional"))
      (node (ref "U$18") (pin "6") (pinfunction "GND_6") (pintype "bidirectional"))
      (node (ref "U$18") (pin "7") (pinfunction "GND_7") (pintype "bidirectional"))
      (node (ref "U$18") (pin "8") (pinfunction "GND_8") (pintype "bidirectional"))
      (node (ref "U$19") (pin "2") (pinfunction "2_2") (pintype "bidirectional"))
      (node (ref "U$2") (pin "3") (pinfunction "GND_3") (pintype "bidirectional"))
      (node (ref "U$2") (pin "4") (pinfunction "GND_4") (pintype "bidirectional"))
      (node (ref "U$2") (pin "5") (pinfunction "GND_5") (pintype "bidirectional"))
      (node (ref "U$2") (pin "6") (pinfunction "GND_6") (pintype "bidirectional"))
      (node (ref "U$2") (pin "7") (pinfunction "GND_7") (pintype "bidirectional"))
      (node (ref "U$2") (pin "8") (pinfunction "GND_8") (pintype "bidirectional"))
      (node (ref "U$20") (pin "3") (pinfunction "GND_3") (pintype "bidirectional"))
      (node (ref "U$20") (pin "4") (pinfunction "GND_4") (pintype "bidirectional"))
      (node (ref "U$20") (pin "5") (pinfunction "GND_5") (pintype "bidirectional"))
      (node (ref "U$20") (pin "6") (pinfunction "GND_6") (pintype "bidirectional"))
      (node (ref "U$20") (pin "7") (pinfunction "GND_7") (pintype "bidirectional"))
      (node (ref "U$20") (pin "8") (pinfunction "GND_8") (pintype "bidirectional"))
      (node (ref "U$21") (pin "3") (pinfunction "GND_3") (pintype "bidirectional"))
      (node (ref "U$21") (pin "4") (pinfunction "GND_4") (pintype "bidirectional"))
      (node (ref "U$21") (pin "5") (pinfunction "GND_5") (pintype "bidirectional"))
      (node (ref "U$21") (pin "6") (pinfunction "GND_6") (pintype "bidirectional"))
      (node (ref "U$21") (pin "7") (pinfunction "GND_7") (pintype "bidirectional"))
      (node (ref "U$21") (pin "8") (pinfunction "GND_8") (pintype "bidirectional"))
      (node (ref "U$22") (pin "3") (pinfunction "3_3") (pintype "bidirectional"))
      (node (ref "U$23") (pin "3") (pinfunction "GND_3") (pintype "bidirectional"))
      (node (ref "U$23") (pin "4") (pinfunction "GND_4") (pintype "bidirectional"))
      (node (ref "U$23") (pin "5") (pinfunction "GND_5") (pintype "bidirectional"))
      (node (ref "U$23") (pin "6") (pinfunction "GND_6") (pintype "bidirectional"))
      (node (ref "U$23") (pin "7") (pinfunction "GND_7") (pintype "bidirectional"))
      (node (ref "U$23") (pin "8") (pinfunction "GND_8") (pintype "bidirectional"))
      (node (ref "U$24") (pin "3") (pinfunction "GND_3") (pintype "bidirectional"))
      (node (ref "U$24") (pin "4") (pinfunction "GND_4") (pintype "bidirectional"))
      (node (ref "U$24") (pin "5") (pinfunction "GND_5") (pintype "bidirectional"))
      (node (ref "U$24") (pin "6") (pinfunction "GND_6") (pintype "bidirectional"))
      (node (ref "U$24") (pin "7") (pinfunction "GND_7") (pintype "bidirectional"))
      (node (ref "U$24") (pin "8") (pinfunction "GND_8") (pintype "bidirectional"))
      (node (ref "U$25") (pin "3") (pinfunction "GND_3") (pintype "bidirectional"))
      (node (ref "U$25") (pin "4") (pinfunction "GND_4") (pintype "bidirectional"))
      (node (ref "U$25") (pin "5") (pinfunction "GND_5") (pintype "bidirectional"))
      (node (ref "U$25") (pin "6") (pinfunction "GND_6") (pintype "bidirectional"))
      (node (ref "U$25") (pin "7") (pinfunction "GND_7") (pintype "bidirectional"))
      (node (ref "U$25") (pin "8") (pinfunction "GND_8") (pintype "bidirectional"))
      (node (ref "U$26") (pin "3") (pinfunction "GND_3") (pintype "bidirectional"))
      (node (ref "U$26") (pin "4") (pinfunction "GND_4") (pintype "bidirectional"))
      (node (ref "U$26") (pin "5") (pinfunction "GND_5") (pintype "bidirectional"))
      (node (ref "U$26") (pin "6") (pinfunction "GND_6") (pintype "bidirectional"))
      (node (ref "U$26") (pin "7") (pinfunction "GND_7") (pintype "bidirectional"))
      (node (ref "U$26") (pin "8") (pinfunction "GND_8") (pintype "bidirectional"))
      (node (ref "U$27") (pin "3") (pinfunction "GND_3") (pintype "bidirectional"))
      (node (ref "U$27") (pin "4") (pinfunction "GND_4") (pintype "bidirectional"))
      (node (ref "U$27") (pin "5") (pinfunction "GND_5") (pintype "bidirectional"))
      (node (ref "U$27") (pin "6") (pinfunction "GND_6") (pintype "bidirectional"))
      (node (ref "U$27") (pin "7") (pinfunction "GND_7") (pintype "bidirectional"))
      (node (ref "U$27") (pin "8") (pinfunction "GND_8") (pintype "bidirectional"))
      (node (ref "U$3") (pin "3") (pinfunction "GND_3") (pintype "bidirectional"))
      (node (ref "U$3") (pin "4") (pinfunction "GND_4") (pintype "bidirectional"))
      (node (ref "U$3") (pin "5") (pinfunction "GND_5") (pintype "bidirectional"))
      (node (ref "U$3") (pin "6") (pinfunction "GND_6") (pintype "bidirectional"))
      (node (ref "U$3") (pin "7") (pinfunction "GND_7") (pintype "bidirectional"))
      (node (ref "U$3") (pin "8") (pinfunction "GND_8") (pintype "bidirectional"))
      (node (ref "U$4") (pin "3") (pinfunction "GND_3") (pintype "bidirectional"))
      (node (ref "U$4") (pin "4") (pinfunction "GND_4") (pintype "bidirectional"))
      (node (ref "U$4") (pin "5") (pinfunction "GND_5") (pintype "bidirectional"))
      (node (ref "U$4") (pin "6") (pinfunction "GND_6") (pintype "bidirectional"))
      (node (ref "U$4") (pin "7") (pinfunction "GND_7") (pintype "bidirectional"))
      (node (ref "U$4") (pin "8") (pinfunction "GND_8") (pintype "bidirectional"))
      (node (ref "U$5") (pin "3") (pinfunction "GND_3") (pintype "bidirectional"))
      (node (ref "U$5") (pin "4") (pinfunction "GND_4") (pintype "bidirectional"))
      (node (ref "U$5") (pin "5") (pinfunction "GND_5") (pintype "bidirectional"))
      (node (ref "U$5") (pin "6") (pinfunction "GND_6") (pintype "bidirectional"))
      (node (ref "U$5") (pin "7") (pinfunction "GND_7") (pintype "bidirectional"))
      (node (ref "U$5") (pin "8") (pinfunction "GND_8") (pintype "bidirectional"))
      (node (ref "U$6") (pin "3") (pinfunction "GND_3") (pintype "bidirectional"))
      (node (ref "U$6") (pin "4") (pinfunction "GND_4") (pintype "bidirectional"))
      (node (ref "U$6") (pin "5") (pinfunction "GND_5") (pintype "bidirectional"))
      (node (ref "U$6") (pin "6") (pinfunction "GND_6") (pintype "bidirectional"))
      (node (ref "U$6") (pin "7") (pinfunction "GND_7") (pintype "bidirectional"))
      (node (ref "U$6") (pin "8") (pinfunction "GND_8") (pintype "bidirectional"))
      (node (ref "U$7") (pin "3") (pinfunction "GND_3") (pintype "bidirectional"))
      (node (ref "U$7") (pin "4") (pinfunction "GND_4") (pintype "bidirectional"))
      (node (ref "U$7") (pin "5") (pinfunction "GND_5") (pintype "bidirectional"))
      (node (ref "U$7") (pin "6") (pinfunction "GND_6") (pintype "bidirectional"))
      (node (ref "U$7") (pin "7") (pinfunction "GND_7") (pintype "bidirectional"))
      (node (ref "U$7") (pin "8") (pinfunction "GND_8") (pintype "bidirectional"))
      (node (ref "U$8") (pin "3") (pinfunction "GND_3") (pintype "bidirectional"))
      (node (ref "U$8") (pin "4") (pinfunction "GND_4") (pintype "bidirectional"))
      (node (ref "U$8") (pin "5") (pinfunction "GND_5") (pintype "bidirectional"))
      (node (ref "U$8") (pin "6") (pinfunction "GND_6") (pintype "bidirectional"))
      (node (ref "U$8") (pin "7") (pinfunction "GND_7") (pintype "bidirectional"))
      (node (ref "U$8") (pin "8") (pinfunction "GND_8") (pintype "bidirectional"))
      (node (ref "U$9") (pin "3") (pinfunction "GND_3") (pintype "bidirectional"))
      (node (ref "U$9") (pin "4") (pinfunction "GND_4") (pintype "bidirectional"))
      (node (ref "U$9") (pin "5") (pinfunction "GND_5") (pintype "bidirectional"))
      (node (ref "U$9") (pin "6") (pinfunction "GND_6") (pintype "bidirectional"))
      (node (ref "U$9") (pin "7") (pinfunction "GND_7") (pintype "bidirectional"))
      (node (ref "U$9") (pin "8") (pinfunction "GND_8") (pintype "bidirectional"))
    )
    (net (code "7") (name "Net-(D1-Pad+)") (class "Default")
      (node (ref "D1") (pin "+") (pinfunction "+_+") (pintype "passive"))
      (node (ref "R1") (pin "2") (pinfunction "2_2") (pintype "bidirectional"))
    )
    (net (code "8") (name "Net-(D2-Pad+)") (class "Default")
      (node (ref "D2") (pin "+") (pinfunction "+_+") (pintype "passive"))
      (node (ref "R2") (pin "2") (pinfunction "2_2") (pintype "bidirectional"))
    )
    (net (code "9") (name "Net-(D3-Pad+)") (class "Default")
      (node (ref "D3") (pin "+") (pinfunction "+_+") (pintype "passive"))
      (node (ref "R3") (pin "2") (pinfunction "2_2") (pintype "bidirectional"))
    )
  )
)
